# tape_smd.net
KiCad netlist of a schematic drawn in EAGLE
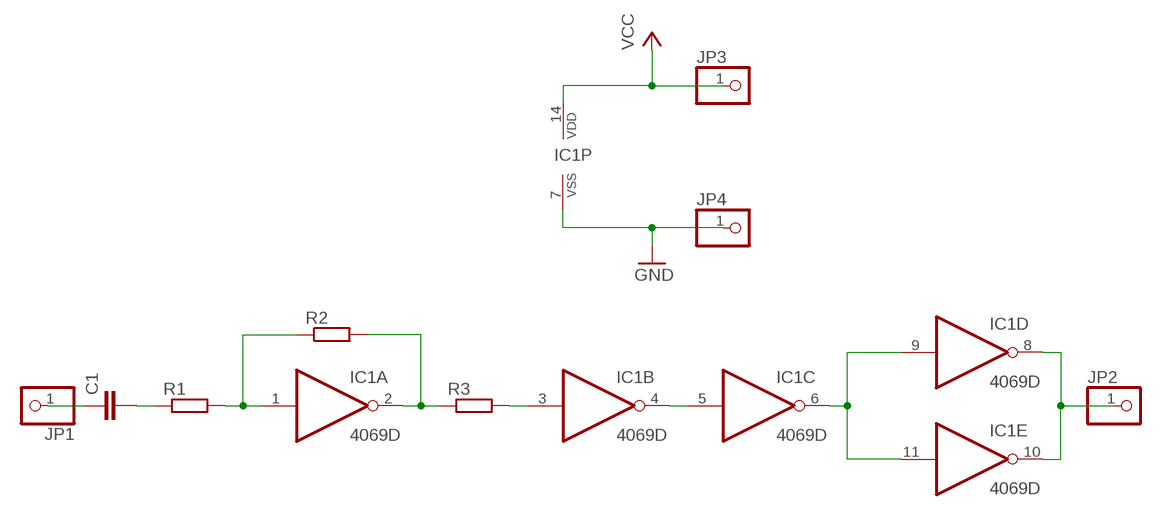
[diagram p0: schematic, sheet 1]

(export (version "E")
  (design (tool "Eeschema 10.0.6"))
  (components
    (comp (ref "C1")
      (value "C-EUC0805")
      (footprint "eagle-import:C0805")
      (libsource (lib "eagle-import") (part "C-EUC0805"))
    )
    (comp (ref "IC1")
      (value "4069D")
      (footprint "eagle-import:SO14")
      (libsource (lib "eagle-import") (part "4069D"))
    )
    (comp (ref "JP1")
      (value "PINHD-1X1")
      (footprint "eagle-import:1X01")
      (libsource (lib "eagle-import") (part "PINHD-1X1"))
    )
    (comp (ref "JP2")
      (value "PINHD-1X1")
      (footprint "eagle-import:1X01")
      (libsource (lib "eagle-import") (part "PINHD-1X1"))
    )
    (comp (ref "JP3")
      (value "PINHD-1X1")
      (footprint "eagle-import:1X01")
      (libsource (lib "eagle-import") (part "PINHD-1X1"))
    )
    (comp (ref "JP4")
      (value "PINHD-1X1")
      (footprint "eagle-import:1X01")
      (libsource (lib "eagle-import") (part "PINHD-1X1"))
    )
    (comp (ref "R1")
      (value "R-EU_R0805")
      (footprint "eagle-import:R0805")
      (libsource (lib "eagle-import") (part "R-EU_R0805"))
    )
    (comp (ref "R2")
      (value "R-EU_R0805")
      (footprint "eagle-import:R0805")
      (libsource (lib "eagle-import") (part "R-EU_R0805"))
    )
    (comp (ref "R3")
      (value "R-EU_R0805")
      (footprint "eagle-import:R0805")
      (libsource (lib "eagle-import") (part "R-EU_R0805"))
    )
  )
  (nets
    (net (code "1") (name "GND") (class "Default")
      (node (ref "IC1") (pin "7") (pinfunction "VSS_7") (pintype "power_in"))
      (node (ref "JP4") (pin "1") (pinfunction "1_1") (pintype "passive"))
    )
    (net (code "2") (name "Net-(C1-Pad1)") (class "Default")
      (node (ref "C1") (pin "1") (pinfunction "1_1") (pintype "passive"))
      (node (ref "JP1") (pin "1") (pinfunction "1_1") (pintype "passive"))
    )
    (net (code "3") (name "Net-(C1-Pad2)") (class "Default")
      (node (ref "C1") (pin "2") (pinfunction "2_2") (pintype "passive"))
      (node (ref "R1") (pin "1") (pinfunction "1_1") (pintype "passive"))
    )
    (net (code "4") (name "Net-(IC1A-I)") (class "Default")
      (node (ref "IC1") (pin "1") (pinfunction "I_1") (pintype "input"))
      (node (ref "R1") (pin "2") (pinfunction "2_2") (pintype "passive"))
      (node (ref "R2") (pin "1") (pinfunction "1_1") (pintype "passive"))
    )
    (net (code "5") (name "Net-(IC1A-O)") (class "Default")
      (node (ref "IC1") (pin "2") (pinfunction "O_2") (pintype "output"))
      (node (ref "R2") (pin "2") (pinfunction "2_2") (pintype "passive"))
      (node (ref "R3") (pin "1") (pinfunction "1_1") (pintype "passive"))
    )
    (net (code "6") (name "Net-(IC1B-I)") (class "Default")
      (node (ref "IC1") (pin "3") (pinfunction "I_3") (pintype "input"))
      (node (ref "R3") (pin "2") (pinfunction "2_2") (pintype "passive"))
    )
    (net (code "7") (name "Net-(IC1B-O)") (class "Default")
      (node (ref "IC1") (pin "4") (pinfunction "O_4") (pintype "output"))
      (node (ref "IC1") (pin "5") (pinfunction "I_5") (pintype "input"))
    )
    (net (code "8") (name "Net-(IC1C-O)") (class "Default")
      (node (ref "IC1") (pin "11") (pinfunction "I_11") (pintype "input"))
      (node (ref "IC1") (pin "6") (pinfunction "O_6") (pintype "output"))
      (node (ref "IC1") (pin "9") (pinfunction "I_9") (pintype "input"))
    )
    (net (code "9") (name "Net-(IC1D-O)") (class "Default")
      (node (ref "IC1") (pin "10") (pinfunction "O_10") (pintype "output"))
      (node (ref "IC1") (pin "8") (pinfunction "O_8") (pintype "output"))
      (node (ref "JP2") (pin "1") (pinfunction "1_1") (pintype "passive"))
    )
    (net (code "10") (name "VCC") (class "Default")
      (node (ref "IC1") (pin "14") (pinfunction "VDD_14") (pintype "power_in"))
      (node (ref "JP3") (pin "1") (pinfunction "1_1") (pintype "passive"))
    )
  )
)
